# SparkFun_Qwiic_CO2_Sensor_XENSIV_PAS.net
KiCad netlist of a schematic drawn in EAGLE
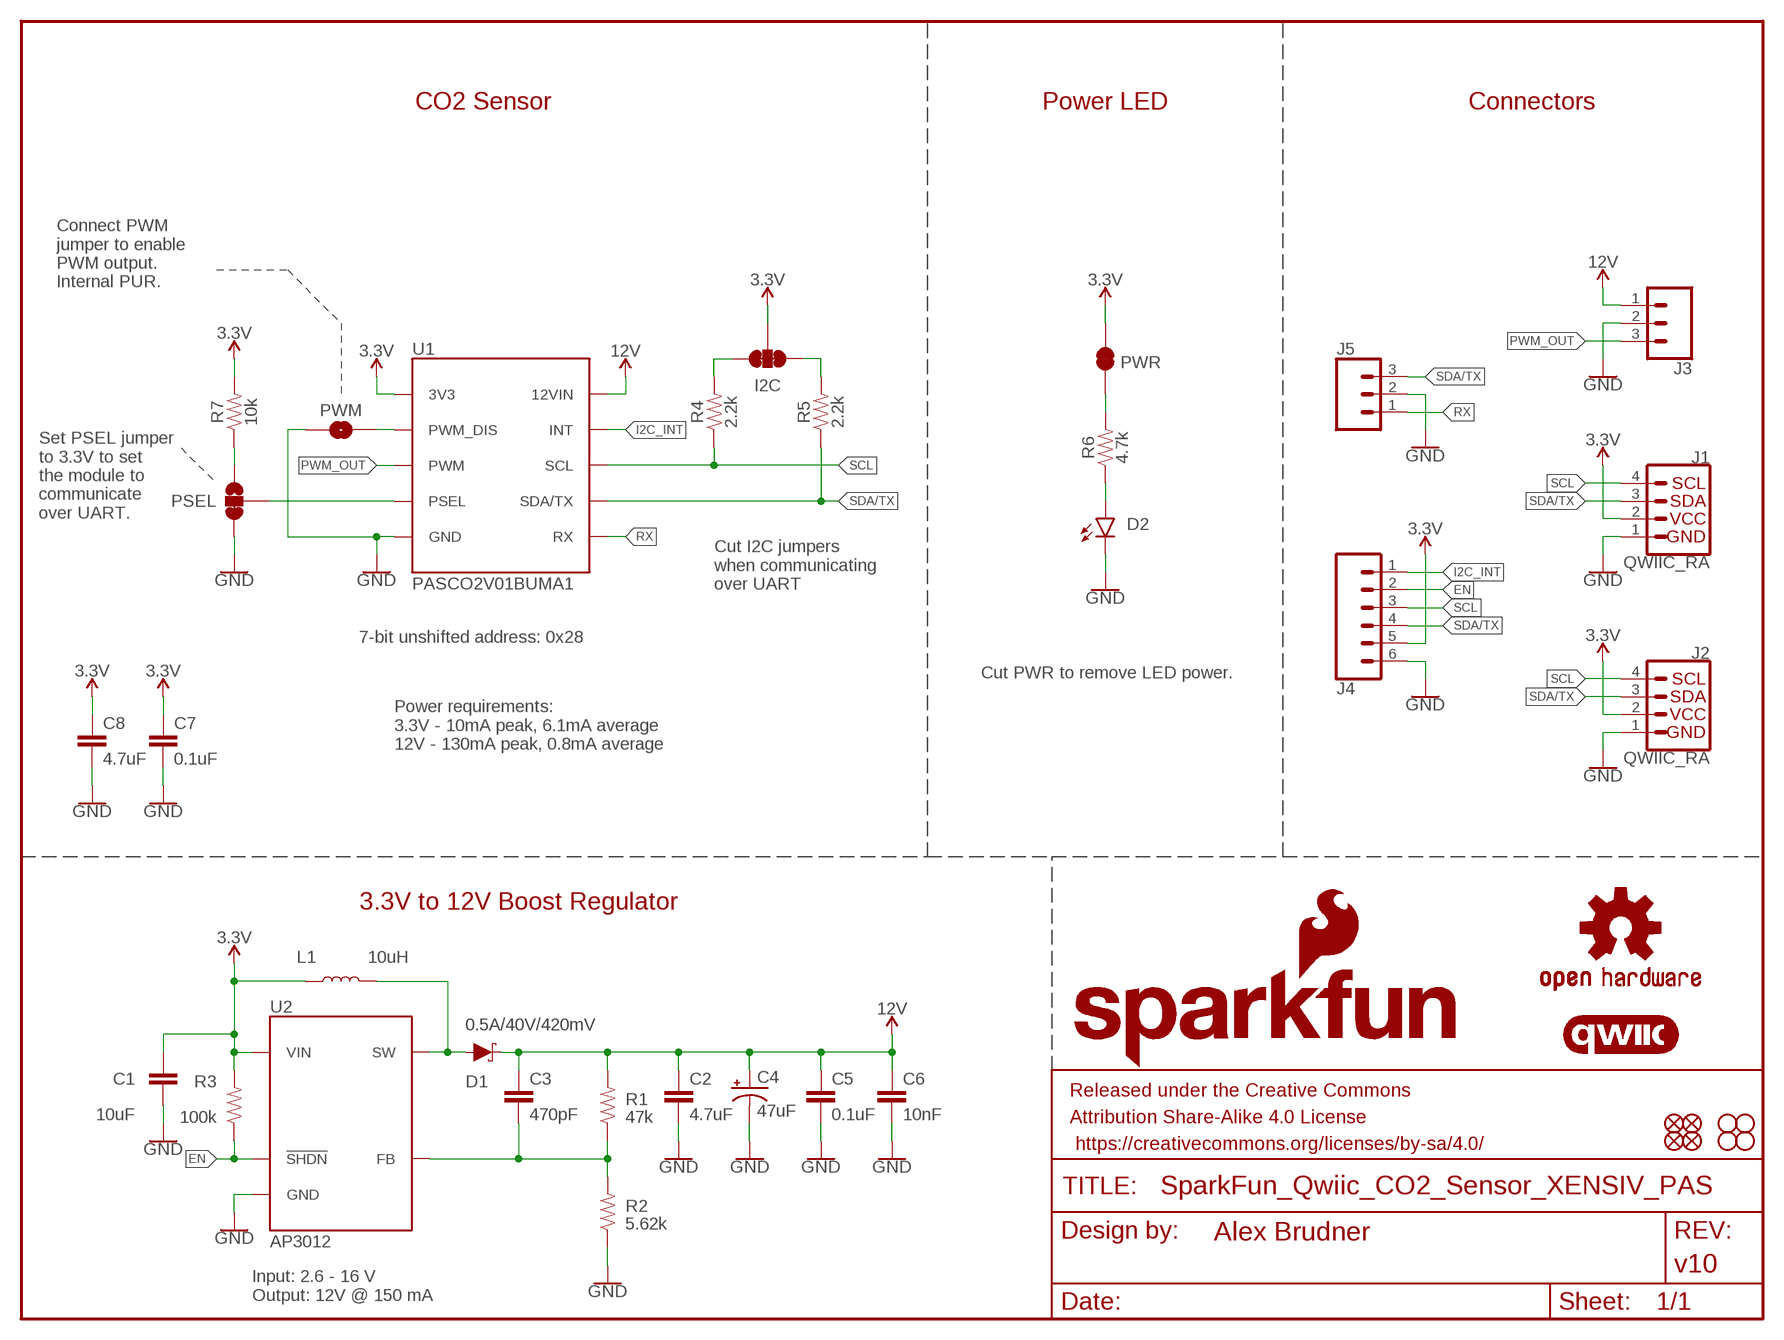
[diagram p0: schematic, sheet 1]

(export (version "E")
  (design (tool "Eeschema 10.0.6"))
  (components
    (comp (ref "C1")
      (value "10uF")
      (footprint "eagle-import:0805")
      (libsource (lib "eagle-import") (part "10UF-0805-25V-10%"))
    )
    (comp (ref "C2")
      (value "4.7uF")
      (footprint "eagle-import:0603")
      (libsource (lib "eagle-import") (part "4.7UF-0603-35V-(20%)"))
    )
    (comp (ref "C3")
      (value "470pF")
      (footprint "eagle-import:0603")
      (libsource (lib "eagle-import") (part "470PF-0603-50V-5%"))
    )
    (comp (ref "C4")
      (value "47uF")
      (footprint "eagle-import:PANASONIC_D")
      (libsource (lib "eagle-import") (part "47UF-POLAR-PANASONIC_D-35V-20%"))
    )
    (comp (ref "C5")
      (value "0.1uF")
      (footprint "eagle-import:0603")
      (libsource (lib "eagle-import") (part "0.1UF-0603-25V-5%"))
    )
    (comp (ref "C6")
      (value "10nF")
      (footprint "eagle-import:0603")
      (libsource (lib "eagle-import") (part "10NF-0603-50V-10%"))
    )
    (comp (ref "C7")
      (value "0.1uF")
      (footprint "eagle-import:0603")
      (libsource (lib "eagle-import") (part "0.1UF-0603-25V-5%"))
    )
    (comp (ref "C8")
      (value "4.7uF")
      (footprint "eagle-import:0603")
      (libsource (lib "eagle-import") (part "4.7UF-0603-35V-(20%)"))
    )
    (comp (ref "D1")
      (value "0.5A/40V/420mV")
      (footprint "eagle-import:SOD-323")
      (libsource (lib "eagle-import") (part "DIODE-SCHOTTKY-PMEG4005EJ"))
    )
    (comp (ref "D2")
      (value "LED-RED_0603-KB")
      (footprint "eagle-import:LED-0603")
      (libsource (lib "eagle-import") (part "LED-RED_0603-KB"))
    )
    (comp (ref "FD1")
      (value "FIDUCIALUFIDUCIAL")
      (footprint "eagle-import:FIDUCIAL-MICRO")
      (libsource (lib "eagle-import") (part "FIDUCIALUFIDUCIAL"))
    )
    (comp (ref "FD2")
      (value "FIDUCIALUFIDUCIAL")
      (footprint "eagle-import:FIDUCIAL-MICRO")
      (libsource (lib "eagle-import") (part "FIDUCIALUFIDUCIAL"))
    )
    (comp (ref "FD3")
      (value "FIDUCIALUFIDUCIAL")
      (footprint "eagle-import:FIDUCIAL-MICRO")
      (libsource (lib "eagle-import") (part "FIDUCIALUFIDUCIAL"))
    )
    (comp (ref "FD4")
      (value "FIDUCIALUFIDUCIAL")
      (footprint "eagle-import:FIDUCIAL-MICRO")
      (libsource (lib "eagle-import") (part "FIDUCIALUFIDUCIAL"))
    )
    (comp (ref "FRAME1")
      (value "FRAME-LETTER")
      (footprint "eagle-import:CREATIVE_COMMONS")
      (fields (field (name "DESIGNER") "Alex Brudner") (field (name "REV") "v10"))
      (libsource (lib "eagle-import") (part "FRAME-LETTER"))
    )
    (comp (ref "H1")
      (value "STAND-OFF")
      (footprint "eagle-import:STAND-OFF")
      (libsource (lib "eagle-import") (part "STAND-OFF"))
    )
    (comp (ref "H2")
      (value "STAND-OFF")
      (footprint "eagle-import:STAND-OFF")
      (libsource (lib "eagle-import") (part "STAND-OFF"))
    )
    (comp (ref "H3")
      (value "STAND-OFF")
      (footprint "eagle-import:STAND-OFF")
      (libsource (lib "eagle-import") (part "STAND-OFF"))
    )
    (comp (ref "H4")
      (value "STAND-OFF")
      (footprint "eagle-import:STAND-OFF")
      (libsource (lib "eagle-import") (part "STAND-OFF"))
    )
    (comp (ref "I2C")
      (value "JUMPER-SMT_3_2-NC_TRACE_SILK")
      (footprint "eagle-import:SMT-JUMPER_3_2-NC_TRACE_SILK")
      (libsource (lib "eagle-import") (part "JUMPER-SMT_3_2-NC_TRACE_SILK"))
    )
    (comp (ref "J1")
      (value "QWIIC_RA")
      (footprint "eagle-import:JST04_1MM_RA")
      (libsource (lib "eagle-import") (part "QWIIC_CONNECTORJS-1MM"))
    )
    (comp (ref "J2")
      (value "QWIIC_RA")
      (footprint "eagle-import:JST04_1MM_RA")
      (libsource (lib "eagle-import") (part "QWIIC_CONNECTORJS-1MM"))
    )
    (comp (ref "J3")
      (value "CONN_031X03_NO_SILK")
      (footprint "eagle-import:1X03_NO_SILK")
      (libsource (lib "eagle-import") (part "CONN_031X03_NO_SILK"))
    )
    (comp (ref "J4")
      (value "CONN_06NO_SILK_NO_POP")
      (footprint "eagle-import:1X06_NO_SILK")
      (libsource (lib "eagle-import") (part "CONN_06NO_SILK_NO_POP"))
    )
    (comp (ref "J5")
      (value "CONN_031X03_NO_SILK")
      (footprint "eagle-import:1X03_NO_SILK")
      (libsource (lib "eagle-import") (part "CONN_031X03_NO_SILK"))
    )
    (comp (ref "L1")
      (value "10uH")
      (footprint "eagle-import:0805")
      (libsource (lib "eagle-import") (part "10UH"))
    )
    (comp (ref "LOGO1")
      (value "SFE_LOGO_NAME_FLAME.1_INCH")
      (footprint "eagle-import:SFE_LOGO_NAME_FLAME_.1")
      (libsource (lib "eagle-import") (part "SFE_LOGO_NAME_FLAME.1_INCH"))
    )
    (comp (ref "LOGO2")
      (value "QWIIC_LOGO_5MM")
      (footprint "eagle-import:QWIIC_5MM")
      (libsource (lib "eagle-import") (part "QWIIC_LOGO_5MM"))
    )
    (comp (ref "LOGO3")
      (value "OSHW-LOGOMINI")
      (footprint "eagle-import:OSHW-LOGO-MINI")
      (libsource (lib "eagle-import") (part "OSHW-LOGOMINI"))
    )
    (comp (ref "PSEL")
      (value "JUMPER-SMT_3_1-NC_TRACE_SILK")
      (footprint "eagle-import:SMT-JUMPER_3_1-NC_TRACE_SILK")
      (libsource (lib "eagle-import") (part "JUMPER-SMT_3_1-NC_TRACE_SILK"))
    )
    (comp (ref "PWM")
      (value "JUMPER-SMT_2_NO_SILK")
      (footprint "eagle-import:SMT-JUMPER_2_NO_SILK")
      (libsource (lib "eagle-import") (part "JUMPER-SMT_2_NO_SILK"))
    )
    (comp (ref "PWR")
      (value "JUMPER-SMT_2_NC_TRACE_SILK")
      (footprint "eagle-import:SMT-JUMPER_2_NC_TRACE_SILK")
      (libsource (lib "eagle-import") (part "JUMPER-SMT_2_NC_TRACE_SILK"))
    )
    (comp (ref "R1")
      (value "47k")
      (footprint "eagle-import:0603")
      (libsource (lib "eagle-import") (part "47KOHM-0603-1/10W-1%"))
    )
    (comp (ref "R2")
      (value "5.62k")
      (footprint "eagle-import:0603")
      (libsource (lib "eagle-import") (part "5.62KOHM-0603-1/10W-1%"))
    )
    (comp (ref "R3")
      (value "100k")
      (footprint "eagle-import:0603")
      (libsource (lib "eagle-import") (part "100KOHM-0603-1/10W-1%"))
    )
    (comp (ref "R4")
      (value "2.2k")
      (footprint "eagle-import:0603")
      (libsource (lib "eagle-import") (part "2.2KOHM-0603-1/10W-1%"))
    )
    (comp (ref "R5")
      (value "2.2k")
      (footprint "eagle-import:0603")
      (libsource (lib "eagle-import") (part "2.2KOHM-0603-1/10W-1%"))
    )
    (comp (ref "R6")
      (value "4.7k")
      (footprint "eagle-import:0603")
      (libsource (lib "eagle-import") (part "4.7KOHM-0603-1/10W-1%"))
    )
    (comp (ref "R7")
      (value "10k")
      (footprint "eagle-import:0603")
      (libsource (lib "eagle-import") (part "10KOHM-0603-1/10W-1%"))
    )
    (comp (ref "U1")
      (value "PASCO2V01BUMA1")
      (footprint "eagle-import:LG-MLGA-14-1_Z8B00206105")
      (libsource (lib "eagle-import") (part "PASCO2V01"))
    )
    (comp (ref "U2")
      (value "AP3012")
      (footprint "eagle-import:SOT95P280X145-5M")
      (fields (field (name "PN") "AP3012"))
      (libsource (lib "eagle-import") (part "AP3012"))
    )
  )
  (nets
    (net (code "1") (name "3.3V") (class "Default")
      (node (ref "C1") (pin "1") (pinfunction "1_1") (pintype "passive"))
      (node (ref "C7") (pin "1") (pinfunction "1_1") (pintype "passive"))
      (node (ref "C8") (pin "1") (pinfunction "1_1") (pintype "passive"))
      (node (ref "I2C") (pin "2") (pinfunction "2_2") (pintype "passive"))
      (node (ref "J1") (pin "2") (pinfunction "2_2") (pintype "power_in"))
      (node (ref "J2") (pin "2") (pinfunction "2_2") (pintype "power_in"))
      (node (ref "J4") (pin "5") (pinfunction "5_5") (pintype "passive"))
      (node (ref "L1") (pin "1") (pinfunction "1_1") (pintype "passive"))
      (node (ref "PWR") (pin "2") (pinfunction "2_2") (pintype "passive"))
      (node (ref "R3") (pin "2") (pinfunction "2_2") (pintype "passive"))
      (node (ref "R7") (pin "2") (pinfunction "2_2") (pintype "passive"))
      (node (ref "U1") (pin "1") (pinfunction "3V3_1") (pintype "bidirectional"))
      (node (ref "U2") (pin "5") (pinfunction "VIN_5") (pintype "bidirectional"))
    )
    (net (code "2") (name "12V") (class "Default")
      (node (ref "C2") (pin "1") (pinfunction "1_1") (pintype "passive"))
      (node (ref "C3") (pin "1") (pinfunction "1_1") (pintype "passive"))
      (node (ref "C4") (pin "+") (pinfunction "+_+") (pintype "passive"))
      (node (ref "C5") (pin "1") (pinfunction "1_1") (pintype "passive"))
      (node (ref "C6") (pin "1") (pinfunction "1_1") (pintype "passive"))
      (node (ref "D1") (pin "C") (pinfunction "C_C") (pintype "passive"))
      (node (ref "J3") (pin "1") (pinfunction "1_1") (pintype "passive"))
      (node (ref "R1") (pin "2") (pinfunction "2_2") (pintype "passive"))
      (node (ref "U1") (pin "10") (pinfunction "12VIN_10") (pintype "bidirectional"))
    )
    (net (code "3") (name "EN") (class "Default")
      (node (ref "J4") (pin "2") (pinfunction "2_2") (pintype "passive"))
      (node (ref "R3") (pin "1") (pinfunction "1_1") (pintype "passive"))
      (node (ref "U2") (pin "4") (pinfunction "~{SHDN}_4") (pintype "bidirectional"))
    )
    (net (code "4") (name "GND") (class "Default")
      (node (ref "C1") (pin "2") (pinfunction "2_2") (pintype "passive"))
      (node (ref "C2") (pin "2") (pinfunction "2_2") (pintype "passive"))
      (node (ref "C4") (pin "-") (pinfunction "-_-") (pintype "passive"))
      (node (ref "C5") (pin "2") (pinfunction "2_2") (pintype "passive"))
      (node (ref "C6") (pin "2") (pinfunction "2_2") (pintype "passive"))
      (node (ref "C7") (pin "2") (pinfunction "2_2") (pintype "passive"))
      (node (ref "C8") (pin "2") (pinfunction "2_2") (pintype "passive"))
      (node (ref "D2") (pin "C") (pinfunction "C_C") (pintype "passive"))
      (node (ref "J1") (pin "1") (pinfunction "1_1") (pintype "power_in"))
      (node (ref "J2") (pin "1") (pinfunction "1_1") (pintype "power_in"))
      (node (ref "J3") (pin "2") (pinfunction "2_2") (pintype "passive"))
      (node (ref "J4") (pin "6") (pinfunction "6_6") (pintype "passive"))
      (node (ref "J5") (pin "2") (pinfunction "2_2") (pintype "passive"))
      (node (ref "PSEL") (pin "3") (pinfunction "3_3") (pintype "passive"))
      (node (ref "PWM") (pin "1") (pinfunction "1_1") (pintype "passive"))
      (node (ref "R2") (pin "1") (pinfunction "1_1") (pintype "passive"))
      (node (ref "U1") (pin "11") (pinfunction "GND_11") (pintype "bidirectional"))
      (node (ref "U1") (pin "12") (pinfunction "GND_12") (pintype "bidirectional"))
      (node (ref "U1") (pin "13") (pinfunction "GND_13") (pintype "bidirectional"))
      (node (ref "U1") (pin "14") (pinfunction "GND_14") (pintype "bidirectional"))
      (node (ref "U1") (pin "6") (pinfunction "GND_6") (pintype "bidirectional"))
      (node (ref "U2") (pin "2") (pinfunction "GND_2") (pintype "bidirectional"))
    )
    (net (code "5") (name "I2C_INT") (class "Default")
      (node (ref "J4") (pin "1") (pinfunction "1_1") (pintype "passive"))
      (node (ref "U1") (pin "7") (pinfunction "INT_7") (pintype "bidirectional"))
    )
    (net (code "6") (name "Net-(D2-PadA)") (class "Default")
      (node (ref "D2") (pin "A") (pinfunction "A_A") (pintype "passive"))
      (node (ref "R6") (pin "1") (pinfunction "1_1") (pintype "passive"))
    )
    (net (code "7") (name "Net-(I2C-Pad1)") (class "Default")
      (node (ref "I2C") (pin "1") (pinfunction "1_1") (pintype "passive"))
      (node (ref "R5") (pin "2") (pinfunction "2_2") (pintype "passive"))
    )
    (net (code "8") (name "Net-(I2C-Pad3)") (class "Default")
      (node (ref "I2C") (pin "3") (pinfunction "3_3") (pintype "passive"))
      (node (ref "R4") (pin "2") (pinfunction "2_2") (pintype "passive"))
    )
    (net (code "9") (name "Net-(PSEL-Pad1)") (class "Default")
      (node (ref "PSEL") (pin "1") (pinfunction "1_1") (pintype "passive"))
      (node (ref "R7") (pin "1") (pinfunction "1_1") (pintype "passive"))
    )
    (net (code "10") (name "Net-(PWR-Pad1)") (class "Default")
      (node (ref "PWR") (pin "1") (pinfunction "1_1") (pintype "passive"))
      (node (ref "R6") (pin "2") (pinfunction "2_2") (pintype "passive"))
    )
    (net (code "11") (name "Net-(U1-PSEL)") (class "Default")
      (node (ref "PSEL") (pin "2") (pinfunction "2_2") (pintype "passive"))
      (node (ref "U1") (pin "8") (pinfunction "PSEL_8") (pintype "bidirectional"))
    )
    (net (code "12") (name "Net-(U1-PWM_DIS)") (class "Default")
      (node (ref "PWM") (pin "2") (pinfunction "2_2") (pintype "passive"))
      (node (ref "U1") (pin "5") (pinfunction "PWM_DIS_5") (pintype "bidirectional"))
    )
    (net (code "13") (name "Net-(U2-FB)") (class "Default")
      (node (ref "C3") (pin "2") (pinfunction "2_2") (pintype "passive"))
      (node (ref "R1") (pin "1") (pinfunction "1_1") (pintype "passive"))
      (node (ref "R2") (pin "2") (pinfunction "2_2") (pintype "passive"))
      (node (ref "U2") (pin "3") (pinfunction "FB_3") (pintype "bidirectional"))
    )
    (net (code "14") (name "Net-(U2-SW)") (class "Default")
      (node (ref "D1") (pin "A") (pinfunction "A_A") (pintype "passive"))
      (node (ref "L1") (pin "2") (pinfunction "2_2") (pintype "passive"))
      (node (ref "U2") (pin "1") (pinfunction "SW_1") (pintype "bidirectional"))
    )
    (net (code "15") (name "PWM_OUT") (class "Default")
      (node (ref "J3") (pin "3") (pinfunction "3_3") (pintype "passive"))
      (node (ref "U1") (pin "9") (pinfunction "PWM_9") (pintype "bidirectional"))
    )
    (net (code "16") (name "RX") (class "Default")
      (node (ref "J5") (pin "1") (pinfunction "1_1") (pintype "passive"))
      (node (ref "U1") (pin "2") (pinfunction "RX_2") (pintype "bidirectional"))
    )
    (net (code "17") (name "SCL") (class "Default")
      (node (ref "J1") (pin "4") (pinfunction "4_4") (pintype "passive"))
      (node (ref "J2") (pin "4") (pinfunction "4_4") (pintype "passive"))
      (node (ref "J4") (pin "3") (pinfunction "3_3") (pintype "passive"))
      (node (ref "R4") (pin "1") (pinfunction "1_1") (pintype "passive"))
      (node (ref "U1") (pin "3") (pinfunction "SCL_3") (pintype "bidirectional"))
    )
    (net (code "18") (name "SDA{slash}TX") (class "Default")
      (node (ref "J1") (pin "3") (pinfunction "3_3") (pintype "passive"))
      (node (ref "J2") (pin "3") (pinfunction "3_3") (pintype "passive"))
      (node (ref "J4") (pin "4") (pinfunction "4_4") (pintype "passive"))
      (node (ref "J5") (pin "3") (pinfunction "3_3") (pintype "passive"))
      (node (ref "R5") (pin "1") (pinfunction "1_1") (pintype "passive"))
      (node (ref "U1") (pin "4") (pinfunction "SDA/TX_4") (pintype "bidirectional"))
    )
  )
)
